# Charger.net
KiCad netlist of a schematic drawn in Altium Designer
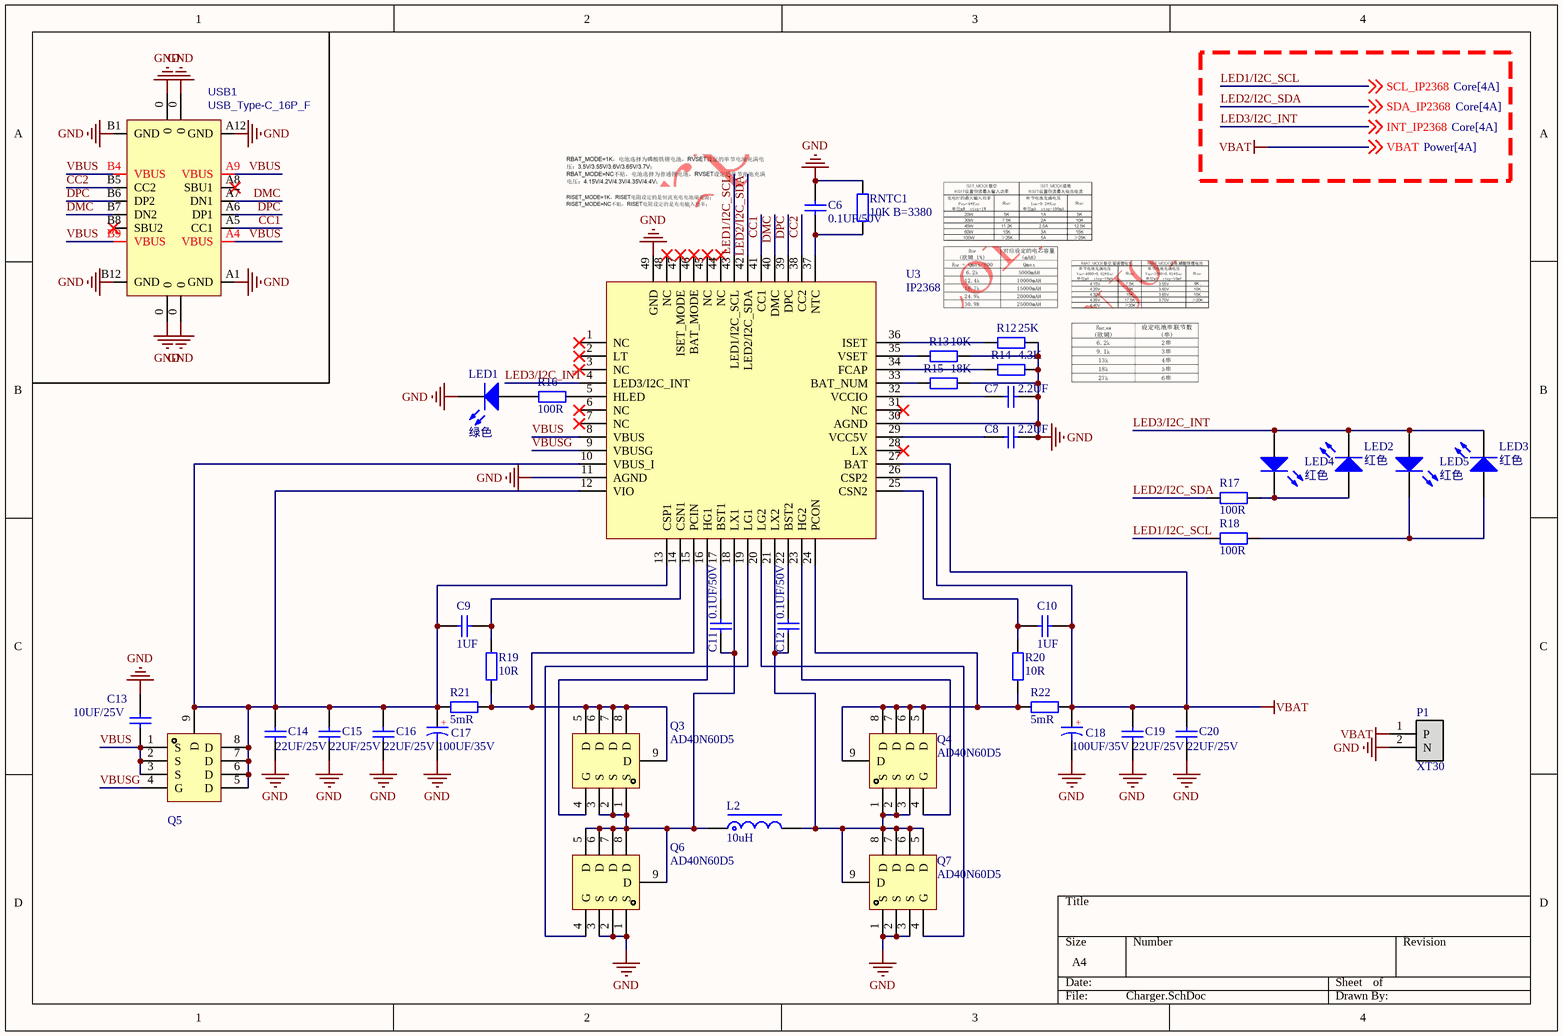
[diagram p0: Charger.SchDoc]

(export (version "E")
  (design (tool "Eeschema 10.0.6"))
  (components
    (comp (ref "C6")
      (value "0.1UF/50V")
      (footprint "C0603_NS")
      (description "贴片电容/MLCC电容")
      (libsource (lib "阻容") (part "C"))
    )
    (comp (ref "C7")
      (value "2.2UF")
      (footprint "C0603_NS")
      (description "贴片电容/MLCC电容")
      (libsource (lib "阻容") (part "C"))
    )
    (comp (ref "C8")
      (value "2.2UF")
      (footprint "C0603_NS")
      (description "贴片电容/MLCC电容")
      (libsource (lib "阻容") (part "C"))
    )
    (comp (ref "C9")
      (value "1UF")
      (footprint "C0402_NS")
      (description "贴片电容/MLCC电容")
      (libsource (lib "阻容") (part "C"))
    )
    (comp (ref "C10")
      (value "1UF")
      (footprint "C0402_NS")
      (description "贴片电容/MLCC电容")
      (libsource (lib "阻容") (part "C"))
    )
    (comp (ref "C11")
      (value "0.1UF/50V")
      (footprint "C0603_NS")
      (description "贴片电容/MLCC电容")
      (libsource (lib "阻容") (part "C"))
    )
    (comp (ref "C12")
      (value "0.1UF/50V")
      (footprint "C0603_NS")
      (description "贴片电容/MLCC电容")
      (libsource (lib "阻容") (part "C"))
    )
    (comp (ref "C13")
      (value "10UF/25V")
      (footprint "C0805_NS")
      (description "贴片电容/MLCC电容")
      (libsource (lib "阻容") (part "C"))
    )
    (comp (ref "C14")
      (value "22UF/25V")
      (footprint "C0805_NS")
      (description "贴片电容/MLCC电容")
      (libsource (lib "阻容") (part "C"))
    )
    (comp (ref "C15")
      (value "22UF/25V")
      (footprint "C0805_NS")
      (description "贴片电容/MLCC电容")
      (libsource (lib "阻容") (part "C"))
    )
    (comp (ref "C16")
      (value "22UF/25V")
      (footprint "C0805_NS")
      (description "贴片电容/MLCC电容")
      (libsource (lib "阻容") (part "C"))
    )
    (comp (ref "C17")
      (value "100UF/35V")
      (footprint "CE D(6.3*7.7)")
      (description "贴片固态电容")
      (libsource (lib "阻容") (part "CE_SMD"))
    )
    (comp (ref "C18")
      (value "100UF/35V")
      (footprint "CE D(6.3*7.7)")
      (description "贴片固态电容")
      (libsource (lib "阻容") (part "CE_SMD"))
    )
    (comp (ref "C19")
      (value "22UF/25V")
      (footprint "C0805_NS")
      (description "贴片电容/MLCC电容")
      (libsource (lib "阻容") (part "C"))
    )
    (comp (ref "C20")
      (value "22UF/25V")
      (footprint "C0805_NS")
      (description "贴片电容/MLCC电容")
      (libsource (lib "阻容") (part "C"))
    )
    (comp (ref "L2")
      (value "10uH")
      (footprint "L-SMD-1040")
      (description "一体成型电感")
      (libsource (lib "电感") (part "L-Molding Choke"))
    )
    (comp (ref "LED1")
      (value "绿色")
      (footprint "LED0603_G")
      (description "贴片LED")
      (libsource (lib "二极管(含LED)") (part "LED"))
    )
    (comp (ref "LED2")
      (value "红色")
      (footprint "LED0603_R")
      (description "贴片LED")
      (libsource (lib "二极管(含LED)") (part "LED"))
    )
    (comp (ref "LED3")
      (value "红色")
      (footprint "LED0603_R")
      (description "贴片LED")
      (libsource (lib "二极管(含LED)") (part "LED"))
    )
    (comp (ref "LED4")
      (value "红色")
      (footprint "LED0603_R")
      (description "贴片LED")
      (libsource (lib "二极管(含LED)") (part "LED"))
    )
    (comp (ref "LED5")
      (value "红色")
      (footprint "LED0603_R")
      (description "贴片LED")
      (libsource (lib "二极管(含LED)") (part "LED"))
    )
    (comp (ref "P1")
      (value "XT30")
      (footprint "XT30PW-M")
      (description "XT30连接器")
      (libsource (lib "接口") (part "XT30"))
    )
    (comp (ref "Q3")
      (value "AD40N60D5")
      (footprint "POWERVDFN8_L6.0_W5.0_P1.27")
      (description "类型:N沟道;漏源电压(Vdss):30V;连续漏极电流(Id):100A;功率(Pd):46.3W;导通电阻(RDS(on)@Vgs,Id):4mΩ@10V,20A;")
      (libsource (lib "三极管-MOS管") (part "WSD30100DN56"))
    )
    (comp (ref "Q4")
      (value "AD40N60D5")
      (footprint "POWERVDFN8_L6.0_W5.0_P1.27")
      (description "类型:N沟道;漏源电压(Vdss):30V;连续漏极电流(Id):100A;功率(Pd):46.3W;导通电阻(RDS(on)@Vgs,Id):4mΩ@10V,20A;")
      (libsource (lib "") (part "WSD30100DN56_1"))
    )
    (comp (ref "Q5")
      (value "AON7544")
      (footprint "DFN8_L3.3_W3.3_P0.65")
      (libsource (lib "三极管-MOS管") (part "AON7544"))
    )
    (comp (ref "Q6")
      (value "AD40N60D5")
      (footprint "POWERVDFN8_L6.0_W5.0_P1.27")
      (description "类型:N沟道;漏源电压(Vdss):30V;连续漏极电流(Id):100A;功率(Pd):46.3W;导通电阻(RDS(on)@Vgs,Id):4mΩ@10V,20A;")
      (libsource (lib "三极管-MOS管") (part "WSD30100DN56"))
    )
    (comp (ref "Q7")
      (value "AD40N60D5")
      (footprint "POWERVDFN8_L6.0_W5.0_P1.27")
      (description "类型:N沟道;漏源电压(Vdss):30V;连续漏极电流(Id):100A;功率(Pd):46.3W;导通电阻(RDS(on)@Vgs,Id):4mΩ@10V,20A;")
      (libsource (lib "") (part "WSD30100DN56_1"))
    )
    (comp (ref "R12")
      (value "25K")
      (footprint "R0402_NS")
      (description "贴片电阻")
      (libsource (lib "阻容") (part "R"))
    )
    (comp (ref "R13")
      (value "10K")
      (footprint "R0402_NS")
      (description "贴片电阻")
      (libsource (lib "阻容") (part "R"))
    )
    (comp (ref "R14")
      (value "4.3K")
      (footprint "R0402_NS")
      (description "贴片电阻")
      (libsource (lib "阻容") (part "R"))
    )
    (comp (ref "R15")
      (value "18K")
      (footprint "R0402_NS")
      (description "贴片电阻")
      (libsource (lib "阻容") (part "R"))
    )
    (comp (ref "R16")
      (value "100R")
      (footprint "R0402_NS")
      (description "贴片电阻")
      (libsource (lib "阻容") (part "R"))
    )
    (comp (ref "R17")
      (value "100R")
      (footprint "R0402_NS")
      (description "贴片电阻")
      (libsource (lib "阻容") (part "R"))
    )
    (comp (ref "R18")
      (value "100R")
      (footprint "R0402_NS")
      (description "贴片电阻")
      (libsource (lib "阻容") (part "R"))
    )
    (comp (ref "R19")
      (value "10R")
      (footprint "R0402_NS")
      (description "贴片电阻")
      (libsource (lib "阻容") (part "R"))
    )
    (comp (ref "R20")
      (value "10R")
      (footprint "R0402_NS")
      (description "贴片电阻")
      (libsource (lib "阻容") (part "R"))
    )
    (comp (ref "R21")
      (value "5mR")
      (footprint "R1206_NS")
      (description "贴片电阻")
      (libsource (lib "阻容") (part "R"))
    )
    (comp (ref "R22")
      (value "5mR")
      (footprint "R1206_NS")
      (description "贴片电阻")
      (libsource (lib "阻容") (part "R"))
    )
    (comp (ref "RNTC1")
      (value "10K B=3380")
      (footprint "R0805_NS")
      (description "贴片电阻")
      (libsource (lib "阻容") (part "R"))
    )
    (comp (ref "U3")
      (value "IP2368")
      (footprint "QFN48_L7.0_W7.0_P0.5")
      (description "支持 PD3.0 等多种快充输入输出协议、支持 2~6 节串联电芯 集成升降压驱动 最大充放电功率 100W 的电源管理芯片")
      (libsource (lib "锂电池管理") (part "IP2368"))
    )
    (comp (ref "USB1")
      (value "USB_Type-C_16P_F")
      (footprint "USB_Type-C_SMD_16P_F")
      (description "USB_Type-C母座")
      (libsource (lib "接口") (part "USB_Type-C_16P_F"))
    )
  )
  (nets
    (net (code "1") (name "/CC1") (class "Default")
      (node (ref "U3") (pin "41") (pinfunction "CC1_41") (pintype "passive"))
      (node (ref "USB1") (pin "A5") (pinfunction "CC1_A5") (pintype "passive"))
    )
    (net (code "2") (name "/CC2") (class "Default")
      (node (ref "U3") (pin "38") (pinfunction "CC2_38") (pintype "passive"))
      (node (ref "USB1") (pin "B5") (pinfunction "CC2_B5") (pintype "passive"))
    )
    (net (code "3") (name "/DMC") (class "Default")
      (node (ref "U3") (pin "40") (pinfunction "DMC_40") (pintype "passive"))
      (node (ref "USB1") (pin "A7") (pinfunction "DN1_A7") (pintype "passive"))
      (node (ref "USB1") (pin "B7") (pinfunction "DN2_B7") (pintype "passive"))
    )
    (net (code "4") (name "/DPC") (class "Default")
      (node (ref "U3") (pin "39") (pinfunction "DPC_39") (pintype "passive"))
      (node (ref "USB1") (pin "A6") (pinfunction "DP1_A6") (pintype "passive"))
      (node (ref "USB1") (pin "B6") (pinfunction "DP2_B6") (pintype "passive"))
    )
    (net (code "5") (name "/VBUS") (class "Default")
      (node (ref "C13") (pin "1") (pinfunction "1_1") (pintype "passive"))
      (node (ref "Q5") (pin "1") (pinfunction "S_1") (pintype "passive"))
      (node (ref "Q5") (pin "2") (pinfunction "S_2") (pintype "passive"))
      (node (ref "Q5") (pin "3") (pinfunction "S_3") (pintype "passive"))
      (node (ref "U3") (pin "8") (pinfunction "VBUS_8") (pintype "passive"))
      (node (ref "USB1") (pin "A4") (pinfunction "VBUS_A4") (pintype "passive"))
      (node (ref "USB1") (pin "A9") (pinfunction "VBUS_A9") (pintype "passive"))
      (node (ref "USB1") (pin "B4") (pinfunction "VBUS_B4") (pintype "passive"))
      (node (ref "USB1") (pin "B9") (pinfunction "VBUS_B9") (pintype "passive"))
    )
    (net (code "6") (name "/VBUSG") (class "Default")
      (node (ref "Q5") (pin "4") (pinfunction "G_4") (pintype "passive"))
      (node (ref "U3") (pin "9") (pinfunction "VBUSG_9") (pintype "passive"))
    )
    (net (code "7") (name "GND") (class "Default")
      (node (ref "C13") (pin "2") (pinfunction "2_2") (pintype "passive"))
      (node (ref "C14") (pin "1") (pinfunction "1_1") (pintype "passive"))
      (node (ref "C15") (pin "1") (pinfunction "1_1") (pintype "passive"))
      (node (ref "C16") (pin "1") (pinfunction "1_1") (pintype "passive"))
      (node (ref "C17") (pin "2") (pinfunction "2_2") (pintype "passive"))
      (node (ref "C18") (pin "2") (pinfunction "2_2") (pintype "passive"))
      (node (ref "C19") (pin "1") (pinfunction "1_1") (pintype "passive"))
      (node (ref "C20") (pin "1") (pinfunction "1_1") (pintype "passive"))
      (node (ref "C6") (pin "2") (pinfunction "2_2") (pintype "passive"))
      (node (ref "C7") (pin "2") (pinfunction "2_2") (pintype "passive"))
      (node (ref "C8") (pin "2") (pinfunction "2_2") (pintype "passive"))
      (node (ref "LED1") (pin "2") (pinfunction "K_2") (pintype "passive"))
      (node (ref "P1") (pin "2") (pinfunction "N_2") (pintype "passive"))
      (node (ref "Q6") (pin "1") (pinfunction "S_1") (pintype "passive"))
      (node (ref "Q6") (pin "2") (pinfunction "S_2") (pintype "passive"))
      (node (ref "Q6") (pin "3") (pinfunction "S_3") (pintype "passive"))
      (node (ref "Q7") (pin "1") (pinfunction "S_1") (pintype "passive"))
      (node (ref "Q7") (pin "2") (pinfunction "S_2") (pintype "passive"))
      (node (ref "Q7") (pin "3") (pinfunction "S_3") (pintype "passive"))
      (node (ref "R12") (pin "2") (pinfunction "2_2") (pintype "passive"))
      (node (ref "R13") (pin "2") (pinfunction "2_2") (pintype "passive"))
      (node (ref "R14") (pin "1") (pinfunction "1_1") (pintype "passive"))
      (node (ref "R15") (pin "1") (pinfunction "1_1") (pintype "passive"))
      (node (ref "RNTC1") (pin "2") (pinfunction "2_2") (pintype "passive"))
      (node (ref "U3") (pin "11") (pinfunction "AGND_11") (pintype "passive"))
      (node (ref "U3") (pin "30") (pinfunction "AGND_30") (pintype "passive"))
      (node (ref "U3") (pin "49") (pinfunction "GND_49") (pintype "passive"))
      (node (ref "USB1") (pin "0") (pinfunction "0_0") (pintype "passive"))
      (node (ref "USB1") (pin "A1") (pinfunction "GND_A1") (pintype "passive"))
      (node (ref "USB1") (pin "A12") (pinfunction "GND_A12") (pintype "passive"))
      (node (ref "USB1") (pin "B1") (pinfunction "GND_B1") (pintype "passive"))
      (node (ref "USB1") (pin "B12") (pinfunction "GND_B12") (pintype "passive"))
    )
    (net (code "8") (name "INT_IP2368") (class "Default")
      (node (ref "LED2") (pin "2") (pinfunction "K_2") (pintype "passive"))
      (node (ref "LED3") (pin "2") (pinfunction "K_2") (pintype "passive"))
      (node (ref "LED4") (pin "1") (pinfunction "A_1") (pintype "passive"))
      (node (ref "LED5") (pin "1") (pinfunction "A_1") (pintype "passive"))
      (node (ref "U3") (pin "4") (pinfunction "LED3/I2C_INT_4") (pintype "passive"))
    )
    (net (code "9") (name "Net-(LED1-A)") (class "Default")
      (node (ref "LED1") (pin "1") (pinfunction "A_1") (pintype "passive"))
      (node (ref "R16") (pin "1") (pinfunction "1_1") (pintype "passive"))
    )
    (net (code "10") (name "Net-(LED2-A)") (class "Default")
      (node (ref "LED2") (pin "1") (pinfunction "A_1") (pintype "passive"))
      (node (ref "LED4") (pin "2") (pinfunction "K_2") (pintype "passive"))
      (node (ref "R17") (pin "2") (pinfunction "2_2") (pintype "passive"))
    )
    (net (code "11") (name "Net-(LED3-A)") (class "Default")
      (node (ref "LED3") (pin "1") (pinfunction "A_1") (pintype "passive"))
      (node (ref "LED5") (pin "2") (pinfunction "K_2") (pintype "passive"))
      (node (ref "R18") (pin "2") (pinfunction "2_2") (pintype "passive"))
    )
    (net (code "12") (name "Net-(Q3-G)") (class "Default")
      (node (ref "Q3") (pin "4") (pinfunction "G_4") (pintype "passive"))
      (node (ref "U3") (pin "16") (pinfunction "HG1_16") (pintype "passive"))
    )
    (net (code "13") (name "Net-(Q4-G)") (class "Default")
      (node (ref "Q4") (pin "4") (pinfunction "G_4") (pintype "passive"))
      (node (ref "U3") (pin "23") (pinfunction "HG2_23") (pintype "passive"))
    )
    (net (code "14") (name "Net-(Q6-G)") (class "Default")
      (node (ref "Q6") (pin "4") (pinfunction "G_4") (pintype "passive"))
      (node (ref "U3") (pin "19") (pinfunction "LG1_19") (pintype "passive"))
    )
    (net (code "15") (name "Net-(Q7-G)") (class "Default")
      (node (ref "Q7") (pin "4") (pinfunction "G_4") (pintype "passive"))
      (node (ref "U3") (pin "20") (pinfunction "LG2_20") (pintype "passive"))
    )
    (net (code "16") (name "Net-(U3-BAT_NUM)") (class "Default")
      (node (ref "R15") (pin "2") (pinfunction "2_2") (pintype "passive"))
      (node (ref "U3") (pin "33") (pinfunction "BAT_NUM_33") (pintype "passive"))
    )
    (net (code "17") (name "Net-(U3-BST1)") (class "Default")
      (node (ref "C11") (pin "2") (pinfunction "2_2") (pintype "passive"))
      (node (ref "U3") (pin "17") (pinfunction "BST1_17") (pintype "passive"))
    )
    (net (code "18") (name "Net-(U3-BST2)") (class "Default")
      (node (ref "C12") (pin "2") (pinfunction "2_2") (pintype "passive"))
      (node (ref "U3") (pin "22") (pinfunction "BST2_22") (pintype "passive"))
    )
    (net (code "19") (name "Net-(U3-CSN1)") (class "Default")
      (node (ref "C9") (pin "2") (pinfunction "2_2") (pintype "passive"))
      (node (ref "R19") (pin "2") (pinfunction "2_2") (pintype "passive"))
      (node (ref "U3") (pin "14") (pinfunction "CSN1_14") (pintype "passive"))
    )
    (net (code "20") (name "Net-(U3-CSN2)") (class "Default")
      (node (ref "C10") (pin "1") (pinfunction "1_1") (pintype "passive"))
      (node (ref "R20") (pin "2") (pinfunction "2_2") (pintype "passive"))
      (node (ref "U3") (pin "25") (pinfunction "CSN2_25") (pintype "passive"))
    )
    (net (code "21") (name "Net-(U3-CSP1)") (class "Default")
      (node (ref "C14") (pin "2") (pinfunction "2_2") (pintype "passive"))
      (node (ref "C15") (pin "2") (pinfunction "2_2") (pintype "passive"))
      (node (ref "C16") (pin "2") (pinfunction "2_2") (pintype "passive"))
      (node (ref "C17") (pin "1") (pinfunction "1_1") (pintype "passive"))
      (node (ref "C9") (pin "1") (pinfunction "1_1") (pintype "passive"))
      (node (ref "Q5") (pin "5") (pinfunction "D_5") (pintype "passive"))
      (node (ref "Q5") (pin "6") (pinfunction "D_6") (pintype "passive"))
      (node (ref "Q5") (pin "7") (pinfunction "D_7") (pintype "passive"))
      (node (ref "Q5") (pin "8") (pinfunction "D_8") (pintype "passive"))
      (node (ref "Q5") (pin "9") (pinfunction "D_9") (pintype "passive"))
      (node (ref "R21") (pin "1") (pinfunction "1_1") (pintype "passive"))
      (node (ref "U3") (pin "10") (pinfunction "VBUS_I_10") (pintype "passive"))
      (node (ref "U3") (pin "12") (pinfunction "VIO_12") (pintype "passive"))
      (node (ref "U3") (pin "13") (pinfunction "CSP1_13") (pintype "passive"))
    )
    (net (code "22") (name "Net-(U3-FCAP)") (class "Default")
      (node (ref "R14") (pin "2") (pinfunction "2_2") (pintype "passive"))
      (node (ref "U3") (pin "34") (pinfunction "FCAP_34") (pintype "passive"))
    )
    (net (code "23") (name "Net-(U3-HLED)") (class "Default")
      (node (ref "R16") (pin "2") (pinfunction "2_2") (pintype "passive"))
      (node (ref "U3") (pin "5") (pinfunction "HLED_5") (pintype "passive"))
    )
    (net (code "24") (name "Net-(U3-ISET)") (class "Default")
      (node (ref "R12") (pin "1") (pinfunction "1_1") (pintype "passive"))
      (node (ref "U3") (pin "36") (pinfunction "ISET_36") (pintype "passive"))
    )
    (net (code "25") (name "Net-(U3-LX1)") (class "Default")
      (node (ref "C11") (pin "1") (pinfunction "1_1") (pintype "passive"))
      (node (ref "L2") (pin "1") (pinfunction "1_1") (pintype "passive"))
      (node (ref "Q3") (pin "1") (pinfunction "S_1") (pintype "passive"))
      (node (ref "Q3") (pin "2") (pinfunction "S_2") (pintype "passive"))
      (node (ref "Q3") (pin "3") (pinfunction "S_3") (pintype "passive"))
      (node (ref "Q6") (pin "5") (pinfunction "D_5") (pintype "passive"))
      (node (ref "Q6") (pin "6") (pinfunction "D_6") (pintype "passive"))
      (node (ref "Q6") (pin "7") (pinfunction "D_7") (pintype "passive"))
      (node (ref "Q6") (pin "8") (pinfunction "D_8") (pintype "passive"))
      (node (ref "Q6") (pin "9") (pinfunction "D_9") (pintype "passive"))
      (node (ref "U3") (pin "18") (pinfunction "LX1_18") (pintype "passive"))
    )
    (net (code "26") (name "Net-(U3-LX2)") (class "Default")
      (node (ref "C12") (pin "1") (pinfunction "1_1") (pintype "passive"))
      (node (ref "L2") (pin "2") (pinfunction "2_2") (pintype "passive"))
      (node (ref "Q4") (pin "1") (pinfunction "S_1") (pintype "passive"))
      (node (ref "Q4") (pin "2") (pinfunction "S_2") (pintype "passive"))
      (node (ref "Q4") (pin "3") (pinfunction "S_3") (pintype "passive"))
      (node (ref "Q7") (pin "5") (pinfunction "D_5") (pintype "passive"))
      (node (ref "Q7") (pin "6") (pinfunction "D_6") (pintype "passive"))
      (node (ref "Q7") (pin "7") (pinfunction "D_7") (pintype "passive"))
      (node (ref "Q7") (pin "8") (pinfunction "D_8") (pintype "passive"))
      (node (ref "Q7") (pin "9") (pinfunction "D_9") (pintype "passive"))
      (node (ref "U3") (pin "21") (pinfunction "LX2_21") (pintype "passive"))
    )
    (net (code "27") (name "Net-(U3-NTC)") (class "Default")
      (node (ref "C6") (pin "1") (pinfunction "1_1") (pintype "passive"))
      (node (ref "RNTC1") (pin "1") (pinfunction "1_1") (pintype "passive"))
      (node (ref "U3") (pin "37") (pinfunction "NTC_37") (pintype "passive"))
    )
    (net (code "28") (name "Net-(U3-PCIN)") (class "Default")
      (node (ref "Q3") (pin "5") (pinfunction "D_5") (pintype "passive"))
      (node (ref "Q3") (pin "6") (pinfunction "D_6") (pintype "passive"))
      (node (ref "Q3") (pin "7") (pinfunction "D_7") (pintype "passive"))
      (node (ref "Q3") (pin "8") (pinfunction "D_8") (pintype "passive"))
      (node (ref "Q3") (pin "9") (pinfunction "D_9") (pintype "passive"))
      (node (ref "R19") (pin "1") (pinfunction "1_1") (pintype "passive"))
      (node (ref "R21") (pin "2") (pinfunction "2_2") (pintype "passive"))
      (node (ref "U3") (pin "15") (pinfunction "PCIN_15") (pintype "passive"))
    )
    (net (code "29") (name "Net-(U3-PCON)") (class "Default")
      (node (ref "Q4") (pin "5") (pinfunction "D_5") (pintype "passive"))
      (node (ref "Q4") (pin "6") (pinfunction "D_6") (pintype "passive"))
      (node (ref "Q4") (pin "7") (pinfunction "D_7") (pintype "passive"))
      (node (ref "Q4") (pin "8") (pinfunction "D_8") (pintype "passive"))
      (node (ref "Q4") (pin "9") (pinfunction "D_9") (pintype "passive"))
      (node (ref "R20") (pin "1") (pinfunction "1_1") (pintype "passive"))
      (node (ref "R22") (pin "1") (pinfunction "1_1") (pintype "passive"))
      (node (ref "U3") (pin "24") (pinfunction "PCON_24") (pintype "passive"))
    )
    (net (code "30") (name "Net-(U3-VCC5V)") (class "Default")
      (node (ref "C8") (pin "1") (pinfunction "1_1") (pintype "passive"))
      (node (ref "U3") (pin "29") (pinfunction "VCC5V_29") (pintype "passive"))
    )
    (net (code "31") (name "Net-(U3-VCCIO)") (class "Default")
      (node (ref "C7") (pin "1") (pinfunction "1_1") (pintype "passive"))
      (node (ref "U3") (pin "32") (pinfunction "VCCIO_32") (pintype "passive"))
    )
    (net (code "32") (name "Net-(U3-VSET)") (class "Default")
      (node (ref "R13") (pin "1") (pinfunction "1_1") (pintype "passive"))
      (node (ref "U3") (pin "35") (pinfunction "VSET_35") (pintype "passive"))
    )
    (net (code "33") (name "SCL_IP2368") (class "Default")
      (node (ref "R18") (pin "1") (pinfunction "1_1") (pintype "passive"))
      (node (ref "U3") (pin "43") (pinfunction "LED1/I2C_SCL_43") (pintype "passive"))
    )
    (net (code "34") (name "SDA_IP2368") (class "Default")
      (node (ref "R17") (pin "1") (pinfunction "1_1") (pintype "passive"))
      (node (ref "U3") (pin "42") (pinfunction "LED2/I2C_SDA_42") (pintype "passive"))
    )
    (net (code "35") (name "VBAT") (class "Default")
      (node (ref "C10") (pin "2") (pinfunction "2_2") (pintype "passive"))
      (node (ref "C18") (pin "1") (pinfunction "1_1") (pintype "passive"))
      (node (ref "C19") (pin "2") (pinfunction "2_2") (pintype "passive"))
      (node (ref "C20") (pin "2") (pinfunction "2_2") (pintype "passive"))
      (node (ref "P1") (pin "1") (pinfunction "P_1") (pintype "passive"))
      (node (ref "R22") (pin "2") (pinfunction "2_2") (pintype "passive"))
      (node (ref "U3") (pin "26") (pinfunction "CSP2_26") (pintype "passive"))
      (node (ref "U3") (pin "27") (pinfunction "BAT_27") (pintype "passive"))
    )
    (net (code "36") (name "unconnected-(U3-BAT_MODE-Pad46)") (class "Default")
      (node (ref "U3") (pin "46") (pinfunction "BAT_MODE_46") (pintype "passive+no_connect"))
    )
    (net (code "37") (name "unconnected-(U3-ISET_MODE-Pad47)") (class "Default")
      (node (ref "U3") (pin "47") (pinfunction "ISET_MODE_47") (pintype "passive+no_connect"))
    )
    (net (code "38") (name "unconnected-(U3-LT-Pad2)") (class "Default")
      (node (ref "U3") (pin "2") (pinfunction "LT_2") (pintype "passive+no_connect"))
    )
    (net (code "39") (name "unconnected-(U3-LX-Pad28)") (class "Default")
      (node (ref "U3") (pin "28") (pinfunction "LX_28") (pintype "passive+no_connect"))
    )
    (net (code "40") (name "unconnected-(U3-NC-Pad1)") (class "Default")
      (node (ref "U3") (pin "1") (pinfunction "NC_1") (pintype "passive+no_connect"))
    )
    (net (code "41") (name "unconnected-(U3-NC-Pad3)") (class "Default")
      (node (ref "U3") (pin "3") (pinfunction "NC_3") (pintype "passive+no_connect"))
    )
    (net (code "42") (name "unconnected-(U3-NC-Pad6)") (class "Default")
      (node (ref "U3") (pin "6") (pinfunction "NC_6") (pintype "passive+no_connect"))
    )
    (net (code "43") (name "unconnected-(U3-NC-Pad7)") (class "Default")
      (node (ref "U3") (pin "7") (pinfunction "NC_7") (pintype "passive+no_connect"))
    )
    (net (code "44") (name "unconnected-(U3-NC-Pad31)") (class "Default")
      (node (ref "U3") (pin "31") (pinfunction "NC_31") (pintype "passive+no_connect"))
    )
    (net (code "45") (name "unconnected-(U3-NC-Pad44)") (class "Default")
      (node (ref "U3") (pin "44") (pinfunction "NC_44") (pintype "passive+no_connect"))
    )
    (net (code "46") (name "unconnected-(U3-NC-Pad45)") (class "Default")
      (node (ref "U3") (pin "45") (pinfunction "NC_45") (pintype "passive+no_connect"))
    )
    (net (code "47") (name "unconnected-(U3-NC-Pad48)") (class "Default")
      (node (ref "U3") (pin "48") (pinfunction "NC_48") (pintype "passive+no_connect"))
    )
    (net (code "48") (name "unconnected-(USB1-SBU1-PadA8)") (class "Default")
      (node (ref "USB1") (pin "A8") (pinfunction "SBU1_A8") (pintype "passive+no_connect"))
    )
    (net (code "49") (name "unconnected-(USB1-SBU2-PadB8)") (class "Default")
      (node (ref "USB1") (pin "B8") (pinfunction "SBU2_B8") (pintype "passive+no_connect"))
    )
  )
)
